# NixiePower.net
KiCad netlist of a schematic drawn in EAGLE
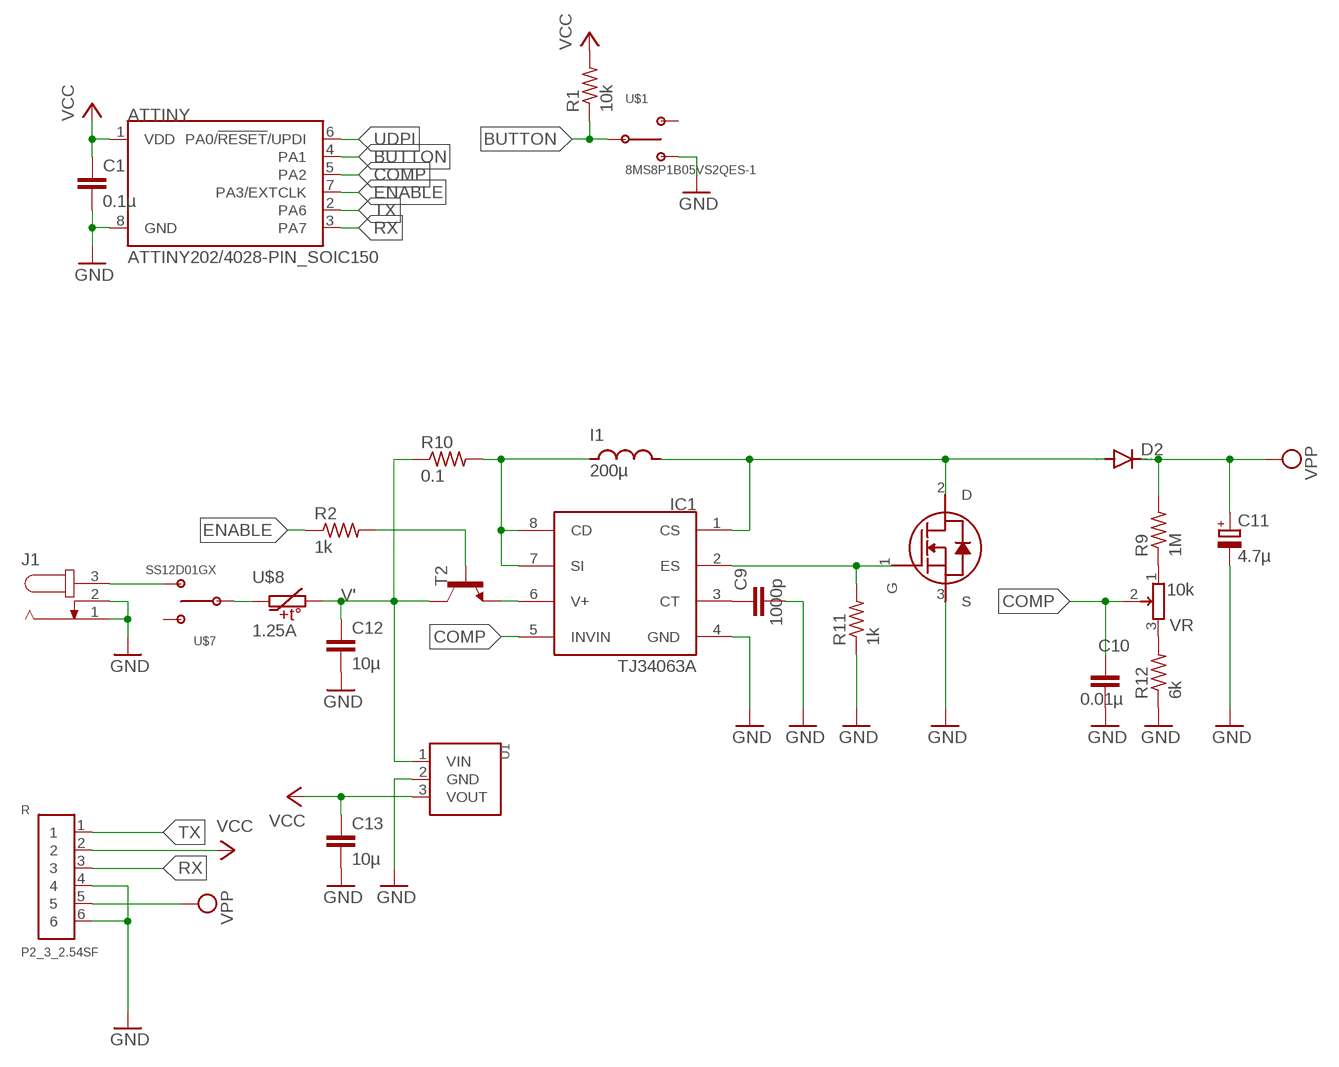
[diagram p0: schematic, sheet 1]

(export (version "E")
  (design (tool "Eeschema 10.0.6"))
  (components
    (comp (ref "ATTINY")
      (value "ATTINY202/4028-PIN_SOIC150")
      (footprint "eagle-import:SOIC127P600X175-8N")
      (libsource (lib "eagle-import") (part "ATTINY202/4028-PIN_SOIC150"))
    )
    (comp (ref "C1")
      (value "0.1µ")
      (footprint "eagle-import:C0603")
      (libsource (lib "eagle-import") (part "C-EUC0603"))
    )
    (comp (ref "C9")
      (value "1000p")
      (footprint "eagle-import:C0603")
      (libsource (lib "eagle-import") (part "resistor_348_C-EUC0603"))
    )
    (comp (ref "C10")
      (value "0.01µ")
      (footprint "eagle-import:C0603")
      (libsource (lib "eagle-import") (part "C-EUC0603"))
    )
    (comp (ref "C11")
      (value "4.7µ")
      (footprint "eagle-import:E5-10,5")
      (libsource (lib "eagle-import") (part "CPOL-EUE5-10.5"))
    )
    (comp (ref "C12")
      (value "10µ")
      (footprint "eagle-import:C0603")
      (libsource (lib "eagle-import") (part "C-EUC0603"))
    )
    (comp (ref "C13")
      (value "10µ")
      (footprint "eagle-import:C0603")
      (libsource (lib "eagle-import") (part "C-EUC0603"))
    )
    (comp (ref "D2")
      (value "DIODE-DO15-12")
      (footprint "eagle-import:DO15-12")
      (libsource (lib "eagle-import") (part "DIODE-DO15-12"))
    )
    (comp (ref "I1")
      (value "200µ")
      (footprint "eagle-import:NR10050")
      (libsource (lib "eagle-import") (part "NR10050"))
    )
    (comp (ref "IC1")
      (value "TJ34063A")
      (footprint "eagle-import:SOP8")
      (libsource (lib "eagle-import") (part "TJ34063A"))
    )
    (comp (ref "J1")
      (value "JACK-PLUG1")
      (footprint "eagle-import:SPC4078")
      (libsource (lib "eagle-import") (part "JACK-PLUG1"))
    )
    (comp (ref "R")
      (value "P2_3_2.54SF")
      (footprint "eagle-import:P2_3_2.54SF")
      (libsource (lib "eagle-import") (part "P2_3_2.54SF"))
    )
    (comp (ref "R1")
      (value "10k")
      (footprint "eagle-import:R0603")
      (libsource (lib "eagle-import") (part "R-US_R0603"))
    )
    (comp (ref "R2")
      (value "1k")
      (footprint "eagle-import:R0603")
      (libsource (lib "eagle-import") (part "R-US_R0603"))
    )
    (comp (ref "R9")
      (value "1M")
      (footprint "eagle-import:R0603")
      (libsource (lib "eagle-import") (part "R-US_R0603"))
    )
    (comp (ref "R10")
      (value "0.1")
      (footprint "eagle-import:R0603")
      (libsource (lib "eagle-import") (part "R-US_R0603"))
    )
    (comp (ref "R11")
      (value "1k")
      (footprint "eagle-import:R0603")
      (libsource (lib "eagle-import") (part "R-US_R0603"))
    )
    (comp (ref "R12")
      (value "6k")
      (footprint "eagle-import:R0603")
      (libsource (lib "eagle-import") (part "R-US_R0603"))
    )
    (comp (ref "T1")
      (value "R6006AND")
      (footprint "eagle-import:CPT3")
      (libsource (lib "eagle-import") (part "R6006AND"))
    )
    (comp (ref "T2")
      (value "-NPN-SOT23-EBC")
      (footprint "eagle-import:SOT23-EBC")
      (libsource (lib "eagle-import") (part "-NPN-SOT23-EBC"))
    )
    (comp (ref "U$1")
      (value "8MS8P1B05VS2QES-1")
      (footprint "eagle-import:8MS8P1B05VS2QES-1")
      (libsource (lib "eagle-import") (part "8MS8P1B05VS2QES-1"))
    )
    (comp (ref "U$7")
      (value "SS12D01GX")
      (footprint "eagle-import:SS12D01GX")
      (libsource (lib "eagle-import") (part "SS12D01GX"))
    )
    (comp (ref "U$8")
      (value "1.25A")
      (footprint "eagle-import:SMD1812P")
      (libsource (lib "eagle-import") (part "SMD1812P125TS"))
    )
    (comp (ref "U1")
      (value "VX078XX-500")
      (footprint "eagle-import:VX078XX-500")
      (libsource (lib "eagle-import") (part "VX078XX-500"))
    )
    (comp (ref "VR")
      (value "10k")
      (footprint "eagle-import:RK09D")
      (libsource (lib "eagle-import") (part "RK09D"))
    )
  )
  (nets
    (net (code "1") (name "/V'") (class "Default")
      (node (ref "C12") (pin "1") (pinfunction "1_1") (pintype "passive"))
      (node (ref "R10") (pin "1") (pinfunction "1_1") (pintype "passive"))
      (node (ref "T2") (pin "C") (pinfunction "C_C") (pintype "passive"))
      (node (ref "U$8") (pin "2") (pinfunction "P2_2") (pintype "bidirectional"))
      (node (ref "U1") (pin "1") (pinfunction "VIN_1") (pintype "bidirectional"))
    )
    (net (code "2") (name "BUTTON") (class "Default")
      (node (ref "ATTINY") (pin "4") (pinfunction "PA1_4") (pintype "bidirectional"))
      (node (ref "R1") (pin "1") (pinfunction "1_1") (pintype "passive"))
      (node (ref "U$1") (pin "2") (pinfunction "C_2") (pintype "bidirectional"))
    )
    (net (code "3") (name "COMP") (class "Default")
      (node (ref "ATTINY") (pin "5") (pinfunction "PA2_5") (pintype "bidirectional"))
      (node (ref "C10") (pin "1") (pinfunction "1_1") (pintype "passive"))
      (node (ref "IC1") (pin "5") (pinfunction "INVIN_5") (pintype "bidirectional"))
      (node (ref "VR") (pin "2") (pinfunction "2_2") (pintype "bidirectional"))
    )
    (net (code "4") (name "ENABLE") (class "Default")
      (node (ref "ATTINY") (pin "7") (pinfunction "PA3/EXTCLK_7") (pintype "bidirectional"))
      (node (ref "R2") (pin "1") (pinfunction "1_1") (pintype "passive"))
    )
    (net (code "5") (name "GND") (class "Default")
      (node (ref "ATTINY") (pin "8") (pinfunction "GND_8") (pintype "power_in"))
      (node (ref "C1") (pin "2") (pinfunction "2_2") (pintype "passive"))
      (node (ref "C10") (pin "2") (pinfunction "2_2") (pintype "passive"))
      (node (ref "C11") (pin "-") (pinfunction "-_-") (pintype "passive"))
      (node (ref "C12") (pin "2") (pinfunction "2_2") (pintype "passive"))
      (node (ref "C13") (pin "2") (pinfunction "2_2") (pintype "passive"))
      (node (ref "C9") (pin "2") (pinfunction "2_2") (pintype "passive"))
      (node (ref "IC1") (pin "4") (pinfunction "GND_4") (pintype "bidirectional"))
      (node (ref "J1") (pin "1") (pinfunction "1_1") (pintype "passive"))
      (node (ref "J1") (pin "2") (pinfunction "2_2") (pintype "passive"))
      (node (ref "R") (pin "4") (pinfunction "4_4") (pintype "bidirectional"))
      (node (ref "R") (pin "6") (pinfunction "6_6") (pintype "bidirectional"))
      (node (ref "R11") (pin "1") (pinfunction "1_1") (pintype "passive"))
      (node (ref "R12") (pin "1") (pinfunction "1_1") (pintype "passive"))
      (node (ref "T1") (pin "3") (pinfunction "S_3") (pintype "bidirectional"))
      (node (ref "U$1") (pin "3") (pinfunction "B_3") (pintype "bidirectional"))
      (node (ref "U1") (pin "2") (pinfunction "GND_2") (pintype "bidirectional"))
    )
    (net (code "6") (name "Net-(IC1-CD)") (class "Default")
      (node (ref "I1") (pin "1") (pinfunction "1_1") (pintype "bidirectional"))
      (node (ref "IC1") (pin "7") (pinfunction "SI_7") (pintype "bidirectional"))
      (node (ref "IC1") (pin "8") (pinfunction "CD_8") (pintype "bidirectional"))
      (node (ref "R10") (pin "2") (pinfunction "2_2") (pintype "passive"))
    )
    (net (code "7") (name "Net-(IC1-CS)") (class "Default")
      (node (ref "D2") (pin "A") (pinfunction "A_A") (pintype "passive"))
      (node (ref "I1") (pin "2") (pinfunction "2_2") (pintype "bidirectional"))
      (node (ref "IC1") (pin "1") (pinfunction "CS_1") (pintype "bidirectional"))
      (node (ref "T1") (pin "2") (pinfunction "D_2") (pintype "bidirectional"))
    )
    (net (code "8") (name "Net-(IC1-CT)") (class "Default")
      (node (ref "C9") (pin "1") (pinfunction "1_1") (pintype "passive"))
      (node (ref "IC1") (pin "3") (pinfunction "CT_3") (pintype "bidirectional"))
    )
    (net (code "9") (name "Net-(IC1-ES)") (class "Default")
      (node (ref "IC1") (pin "2") (pinfunction "ES_2") (pintype "bidirectional"))
      (node (ref "R11") (pin "2") (pinfunction "2_2") (pintype "passive"))
      (node (ref "T1") (pin "1") (pinfunction "G_1") (pintype "bidirectional"))
    )
    (net (code "10") (name "Net-(IC1-V+)") (class "Default")
      (node (ref "IC1") (pin "6") (pinfunction "V+_6") (pintype "bidirectional"))
      (node (ref "T2") (pin "E") (pinfunction "E_E") (pintype "passive"))
    )
    (net (code "11") (name "Net-(R2-Pad2)") (class "Default")
      (node (ref "R2") (pin "2") (pinfunction "2_2") (pintype "passive"))
      (node (ref "T2") (pin "B") (pinfunction "B_B") (pintype "passive"))
    )
    (net (code "12") (name "Net-(U$7-B)") (class "Default")
      (node (ref "J1") (pin "3") (pinfunction "3_3") (pintype "passive"))
      (node (ref "U$7") (pin "3") (pinfunction "B_3") (pintype "bidirectional"))
    )
    (net (code "13") (name "Net-(U$7-C)") (class "Default")
      (node (ref "U$7") (pin "2") (pinfunction "C_2") (pintype "bidirectional"))
      (node (ref "U$8") (pin "1") (pinfunction "P1_1") (pintype "bidirectional"))
    )
    (net (code "14") (name "Net-(VR-1)") (class "Default")
      (node (ref "R12") (pin "2") (pinfunction "2_2") (pintype "passive"))
      (node (ref "VR") (pin "3") (pinfunction "1_3") (pintype "bidirectional"))
    )
    (net (code "15") (name "Net-(VR-3)") (class "Default")
      (node (ref "R9") (pin "1") (pinfunction "1_1") (pintype "passive"))
      (node (ref "VR") (pin "1") (pinfunction "3_1") (pintype "bidirectional"))
    )
    (net (code "16") (name "RX") (class "Default")
      (node (ref "ATTINY") (pin "3") (pinfunction "PA7_3") (pintype "bidirectional"))
      (node (ref "R") (pin "3") (pinfunction "3_3") (pintype "bidirectional"))
    )
    (net (code "17") (name "TX") (class "Default")
      (node (ref "ATTINY") (pin "2") (pinfunction "PA6_2") (pintype "bidirectional"))
      (node (ref "R") (pin "1") (pinfunction "1_1") (pintype "bidirectional"))
    )
    (net (code "18") (name "UDPI") (class "Default")
      (node (ref "ATTINY") (pin "6") (pinfunction "PA0/~{RESET}/UPDI_6") (pintype "bidirectional"))
    )
    (net (code "19") (name "VCC") (class "Default")
      (node (ref "ATTINY") (pin "1") (pinfunction "VDD_1") (pintype "power_in"))
      (node (ref "C1") (pin "1") (pinfunction "1_1") (pintype "passive"))
      (node (ref "C13") (pin "1") (pinfunction "1_1") (pintype "passive"))
      (node (ref "R") (pin "2") (pinfunction "2_2") (pintype "bidirectional"))
      (node (ref "R1") (pin "2") (pinfunction "2_2") (pintype "passive"))
      (node (ref "U1") (pin "3") (pinfunction "VOUT_3") (pintype "bidirectional"))
    )
    (net (code "20") (name "VPP") (class "Default")
      (node (ref "C11") (pin "+") (pinfunction "+_+") (pintype "passive"))
      (node (ref "D2") (pin "C") (pinfunction "C_C") (pintype "passive"))
      (node (ref "R") (pin "5") (pinfunction "5_5") (pintype "bidirectional"))
      (node (ref "R9") (pin "2") (pinfunction "2_2") (pintype "passive"))
    )
    (net (code "21") (name "unconnected-(U$1-A-Pad1)") (class "Default")
      (node (ref "U$1") (pin "1") (pinfunction "A_1") (pintype "bidirectional"))
    )
    (net (code "22") (name "unconnected-(U$7-A-Pad1)") (class "Default")
      (node (ref "U$7") (pin "1") (pinfunction "A_1") (pintype "bidirectional"))
    )
  )
)
